# 32u4_with_A9G_GPRS_GSM_GPS_v1_0.net
KiCad netlist of a schematic drawn in EAGLE
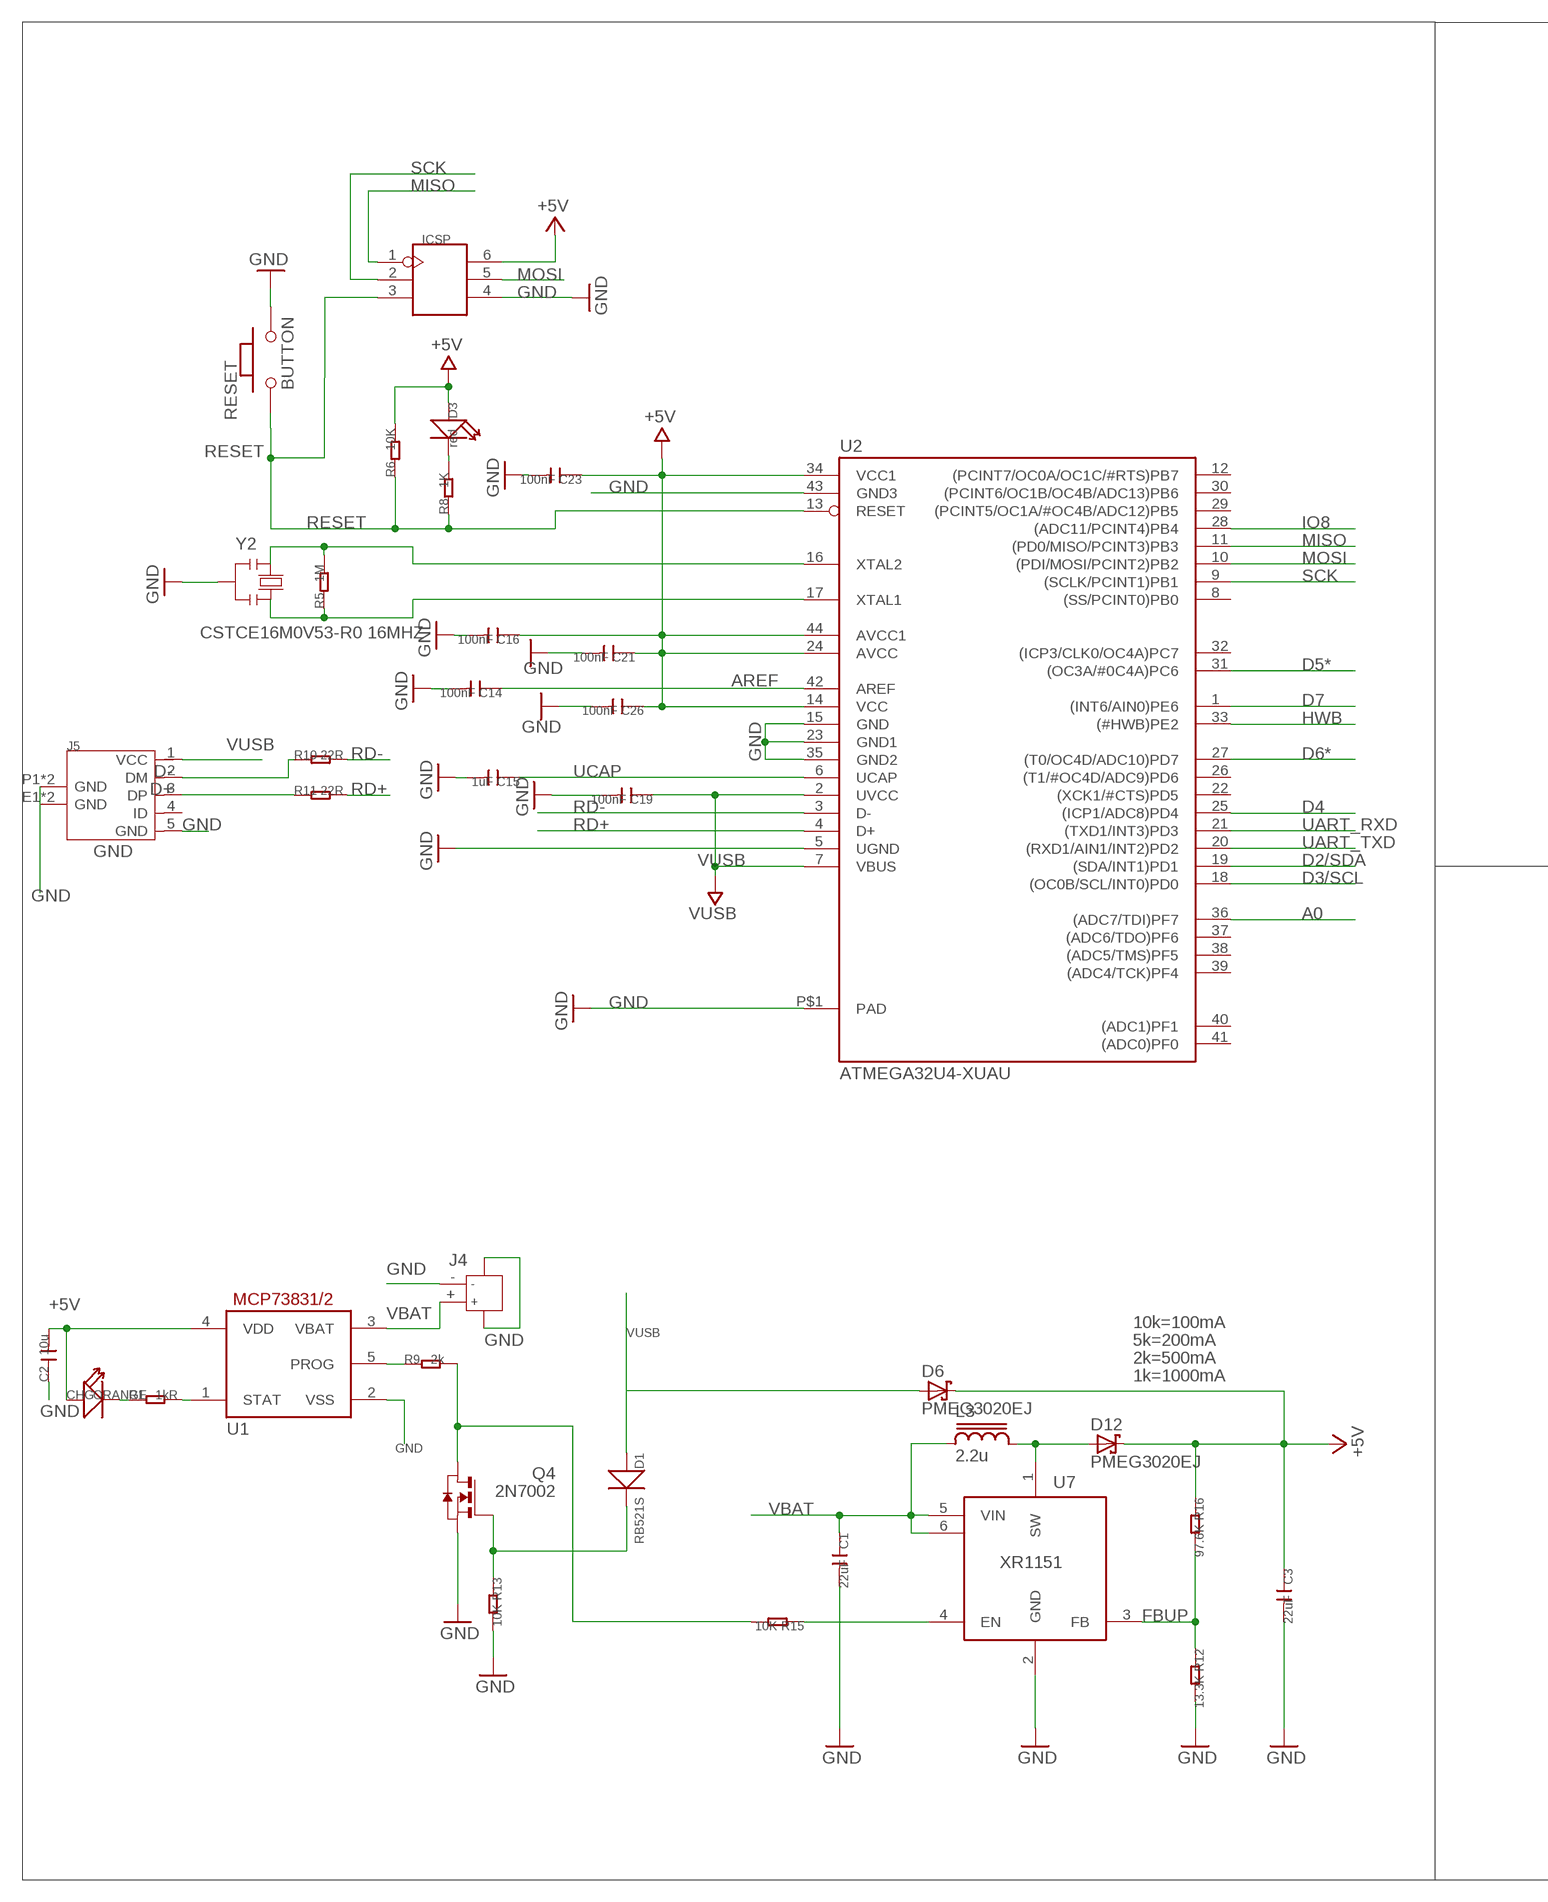
[diagram p0: schematic, sheet 1, part 1 of 2]
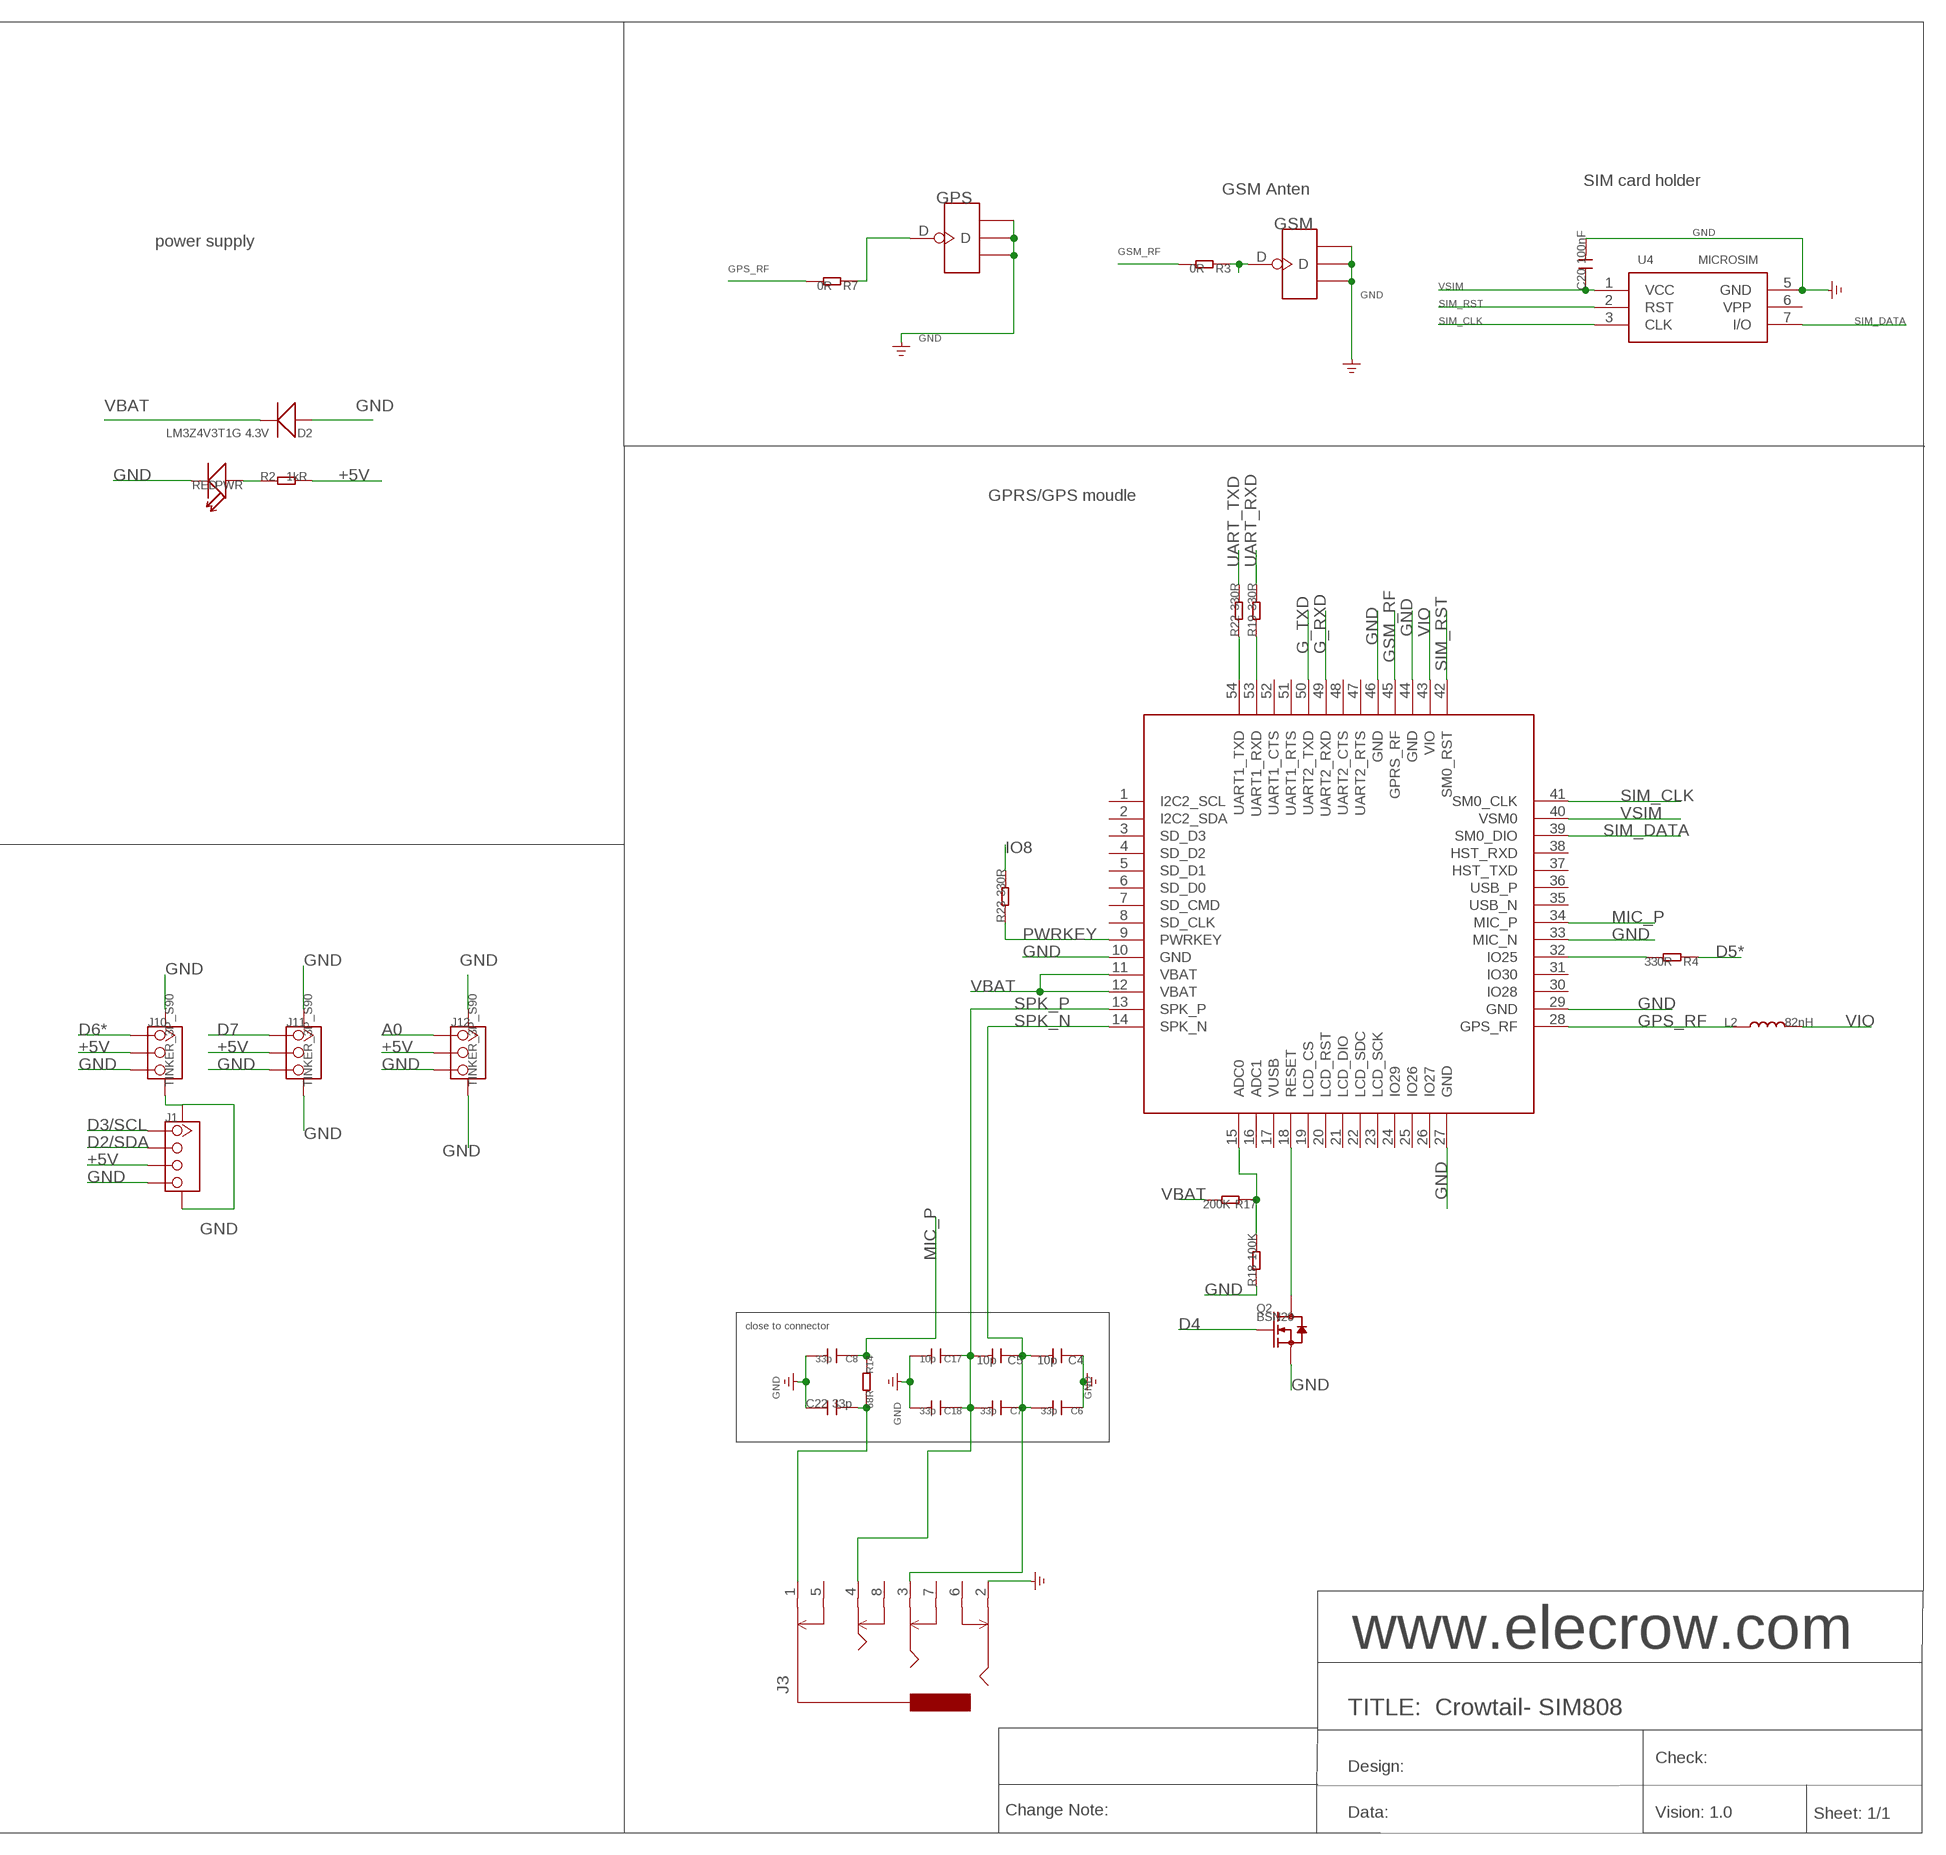
[diagram p1: schematic, sheet 1, part 2 of 2]

(export (version "E")
  (design (tool "Eeschema 10.0.6"))
  (components
    (comp (ref "C1")
      (value "22uF")
      (footprint "eagle-import:C0603")
      (libsource (lib "eagle-import") (part "C-0603"))
    )
    (comp (ref "C2")
      (value "10u")
      (footprint "eagle-import:C0603")
      (libsource (lib "eagle-import") (part "C-0603"))
    )
    (comp (ref "C3")
      (value "22uF")
      (footprint "eagle-import:C0603")
      (libsource (lib "eagle-import") (part "C-0603"))
    )
    (comp (ref "C4")
      (value "10p")
      (footprint "eagle-import:C0402")
      (libsource (lib "eagle-import") (part "C-0402"))
    )
    (comp (ref "C5")
      (value "10p")
      (footprint "eagle-import:C0402")
      (libsource (lib "eagle-import") (part "C-0402"))
    )
    (comp (ref "C6")
      (value "33p")
      (footprint "eagle-import:C0402")
      (libsource (lib "eagle-import") (part "C-0402"))
    )
    (comp (ref "C7")
      (value "33p")
      (footprint "eagle-import:C0402")
      (libsource (lib "eagle-import") (part "C-0402"))
    )
    (comp (ref "C8")
      (value "33p")
      (footprint "eagle-import:C0603")
      (libsource (lib "eagle-import") (part "C-0603"))
    )
    (comp (ref "C14")
      (value "100nF")
      (footprint "eagle-import:C0603")
      (libsource (lib "eagle-import") (part "C-0603"))
    )
    (comp (ref "C15")
      (value "1uF")
      (footprint "eagle-import:C0603")
      (libsource (lib "eagle-import") (part "C-0603"))
    )
    (comp (ref "C16")
      (value "100nF")
      (footprint "eagle-import:C0603")
      (libsource (lib "eagle-import") (part "C-0603"))
    )
    (comp (ref "C17")
      (value "10p")
      (footprint "eagle-import:C0402")
      (libsource (lib "eagle-import") (part "C-0402"))
    )
    (comp (ref "C18")
      (value "33p")
      (footprint "eagle-import:C0402")
      (libsource (lib "eagle-import") (part "C-0402"))
    )
    (comp (ref "C19")
      (value "100nF")
      (footprint "eagle-import:C0603")
      (libsource (lib "eagle-import") (part "C-0603"))
    )
    (comp (ref "C20")
      (value "100nF")
      (footprint "eagle-import:C0603")
      (libsource (lib "eagle-import") (part "C-0603"))
    )
    (comp (ref "C21")
      (value "100nF")
      (footprint "eagle-import:C0603")
      (libsource (lib "eagle-import") (part "C-0603"))
    )
    (comp (ref "C22")
      (value "33p")
      (footprint "eagle-import:C0603")
      (libsource (lib "eagle-import") (part "C-0603"))
    )
    (comp (ref "C23")
      (value "100nF")
      (footprint "eagle-import:C0603")
      (libsource (lib "eagle-import") (part "C-0603"))
    )
    (comp (ref "C26")
      (value "100nF")
      (footprint "eagle-import:C0603")
      (libsource (lib "eagle-import") (part "C-0603"))
    )
    (comp (ref "CHG")
      (value "ORANGE")
      (footprint "eagle-import:D0603")
      (libsource (lib "eagle-import") (part "007-LED0603"))
    )
    (comp (ref "D1")
      (value "RB521S")
      (footprint "eagle-import:SOD523")
      (libsource (lib "eagle-import") (part "D'0603'"))
    )
    (comp (ref "D2")
      (value "LM3Z4V3T1G 4.3V")
      (footprint "eagle-import:SOD323")
      (libsource (lib "eagle-import") (part "D'0805'"))
    )
    (comp (ref "D3")
      (value "red")
      (footprint "eagle-import:LED-0603")
      (libsource (lib "eagle-import") (part "LED'0603'"))
    )
    (comp (ref "D6")
      (value "PMEG3020EJ")
      (footprint "eagle-import:SOD-323")
      (libsource (lib "eagle-import") (part "PMEG3020EJ"))
    )
    (comp (ref "D12")
      (value "PMEG3020EJ")
      (footprint "eagle-import:SOD-323")
      (libsource (lib "eagle-import") (part "PMEG3020EJ"))
    )
    (comp (ref "GPS")
      (value "ANTENNA-U-FL")
      (footprint "eagle-import:4P-U-FL")
      (libsource (lib "eagle-import") (part "ANTENNA-U-FL"))
    )
    (comp (ref "GSM")
      (value "ANTENNA-U-FL")
      (footprint "eagle-import:4P-U-FL")
      (libsource (lib "eagle-import") (part "ANTENNA-U-FL"))
    )
    (comp (ref "ICSP")
      (value "HEADER-2X3P-2.0")
      (footprint "eagle-import:2X3P-2.0")
      (libsource (lib "eagle-import") (part "HEADER-2X3P-2.0"))
    )
    (comp (ref "J1")
      (value "TWIG-4P-2.0-SMD-FEMALE-REINFORCE'90D'")
      (footprint "eagle-import:4P-SMD-2.0-90D")
      (libsource (lib "eagle-import") (part "TWIG-4P-2.0-SMD-FEMALE-REINFORCE'90D'"))
    )
    (comp (ref "J3")
      (value "AUDIO-8P'PJ-3536-L6S'")
      (footprint "eagle-import:8P-3.5-SMD")
      (libsource (lib "eagle-import") (part "AUDIO-8P'PJ-3536-L6S'"))
    )
    (comp (ref "J4")
      (value "JACK-JST-2P-SMD-PW'2.0'")
      (footprint "eagle-import:JST-SMD-2.0-90D")
      (libsource (lib "eagle-import") (part "JACK-JST-2P-SMD-PW'2.0'"))
    )
    (comp (ref "J5")
      (value "MICRO-USB-5P-340015001")
      (footprint "eagle-import:B-SMD-5P")
      (libsource (lib "eagle-import") (part "MICRO-USB-5P-340015001"))
    )
    (comp (ref "J10")
      (value "TINKER_3P_S90")
      (footprint "eagle-import:TINKER_3P_S90")
      (libsource (lib "eagle-import") (part "TINKER_3P_S90"))
    )
    (comp (ref "J11")
      (value "TINKER_3P_S90")
      (footprint "eagle-import:TINKER_3P_S90")
      (libsource (lib "eagle-import") (part "TINKER_3P_S90"))
    )
    (comp (ref "J12")
      (value "TINKER_3P_S90")
      (footprint "eagle-import:TINKER_3P_S90")
      (libsource (lib "eagle-import") (part "TINKER_3P_S90"))
    )
    (comp (ref "L2")
      (value "82nH")
      (footprint "eagle-import:L0603")
      (libsource (lib "eagle-import") (part "L'0603'"))
    )
    (comp (ref "L3")
      (value "2.2u")
      (footprint "eagle-import:CD32")
      (libsource (lib "eagle-import") (part "LCD32"))
    )
    (comp (ref "PWR")
      (value "RED")
      (footprint "eagle-import:D0603")
      (libsource (lib "eagle-import") (part "007-LED0603"))
    )
    (comp (ref "Q2")
      (value "BSN20")
      (footprint "eagle-import:SOT23@1")
      (libsource (lib "eagle-import") (part "MOSFET-N'SOT23'"))
    )
    (comp (ref "Q4")
      (value "2N7002")
      (footprint "eagle-import:SOT23")
      (libsource (lib "eagle-import") (part "2N7002"))
    )
    (comp (ref "R1")
      (value "1kR")
      (footprint "eagle-import:R0603")
      (libsource (lib "eagle-import") (part "R-0603"))
    )
    (comp (ref "R2")
      (value "1kR")
      (footprint "eagle-import:R0603")
      (libsource (lib "eagle-import") (part "R-0603"))
    )
    (comp (ref "R3")
      (value "0R")
      (footprint "eagle-import:R0603")
      (libsource (lib "eagle-import") (part "R-0603"))
    )
    (comp (ref "R4")
      (value "330R")
      (footprint "eagle-import:R0603")
      (libsource (lib "eagle-import") (part "R-0603"))
    )
    (comp (ref "R5")
      (value "1M")
      (footprint "eagle-import:R0603")
      (libsource (lib "eagle-import") (part "R-0603"))
    )
    (comp (ref "R6")
      (value "10K")
      (footprint "eagle-import:R0603")
      (libsource (lib "eagle-import") (part "R-0603"))
    )
    (comp (ref "R7")
      (value "0R")
      (footprint "eagle-import:R0603")
      (libsource (lib "eagle-import") (part "R-0603"))
    )
    (comp (ref "R8")
      (value "1K")
      (footprint "eagle-import:R0603")
      (libsource (lib "eagle-import") (part "R-0603"))
    )
    (comp (ref "R9")
      (value "2k")
      (footprint "eagle-import:R0603")
      (libsource (lib "eagle-import") (part "R-0603"))
    )
    (comp (ref "R10")
      (value "22R")
      (footprint "eagle-import:R0603")
      (libsource (lib "eagle-import") (part "R-0603"))
    )
    (comp (ref "R11")
      (value "22R")
      (footprint "eagle-import:R0603")
      (libsource (lib "eagle-import") (part "R-0603"))
    )
    (comp (ref "R12")
      (value "13.3K")
      (footprint "eagle-import:R0603")
      (libsource (lib "eagle-import") (part "R-0603"))
    )
    (comp (ref "R13")
      (value "10K")
      (footprint "eagle-import:R0603")
      (libsource (lib "eagle-import") (part "R-0603"))
    )
    (comp (ref "R14")
      (value "68R")
      (footprint "eagle-import:R0603")
      (libsource (lib "eagle-import") (part "R-0603"))
    )
    (comp (ref "R15")
      (value "10K")
      (footprint "eagle-import:R0603")
      (libsource (lib "eagle-import") (part "R-0603"))
    )
    (comp (ref "R16")
      (value "97.6K")
      (footprint "eagle-import:R0603")
      (libsource (lib "eagle-import") (part "R-0603"))
    )
    (comp (ref "R17")
      (value "200K")
      (footprint "eagle-import:R0603")
      (libsource (lib "eagle-import") (part "R-0603"))
    )
    (comp (ref "R18")
      (value "100K")
      (footprint "eagle-import:R0603")
      (libsource (lib "eagle-import") (part "R-0603"))
    )
    (comp (ref "R19")
      (value "330R")
      (footprint "eagle-import:R0603")
      (libsource (lib "eagle-import") (part "R-0603"))
    )
    (comp (ref "R22")
      (value "330R")
      (footprint "eagle-import:R0603")
      (libsource (lib "eagle-import") (part "R-0603"))
    )
    (comp (ref "R23")
      (value "330R")
      (footprint "eagle-import:R0603")
      (libsource (lib "eagle-import") (part "R-0603"))
    )
    (comp (ref "RESET")
      (value "BUTTON")
      (footprint "eagle-import:157SW")
      (libsource (lib "eagle-import") (part "PB157"))
    )
    (comp (ref "U1")
      (value "MCP73831/OT")
      (footprint "eagle-import:SOT23-5L")
      (libsource (lib "eagle-import") (part "MCP73831/OT"))
    )
    (comp (ref "U2")
      (value "ATMEGA32U4-XUAU")
      (footprint "eagle-import:TQFP44-PAD")
      (libsource (lib "eagle-import") (part "ATMEGA32U4-XUAU"))
    )
    (comp (ref "U4")
      (value "MICROSIM")
      (footprint "eagle-import:MICROSIM")
      (libsource (lib "eagle-import") (part "MICROSIM"))
    )
    (comp (ref "U5")
      (value "A9G")
      (footprint "eagle-import:A9G")
      (libsource (lib "eagle-import") (part "A9G"))
    )
    (comp (ref "U7")
      (value "XR1151")
      (footprint "eagle-import:SOT23-6L")
      (libsource (lib "eagle-import") (part "XR1151"))
    )
    (comp (ref "Y2")
      (value "CSTCE16M0V53-R0 16MHZ")
      (footprint "eagle-import:RESONATOR")
      (libsource (lib "eagle-import") (part "RESONATORMU"))
    )
  )
  (nets
    (net (code "1") (name "+5V") (class "Default")
      (node (ref "C16") (pin "1") (pinfunction "1_1") (pintype "passive"))
      (node (ref "C2") (pin "2") (pinfunction "2_2") (pintype "passive"))
      (node (ref "C21") (pin "1") (pinfunction "1_1") (pintype "passive"))
      (node (ref "C23") (pin "1") (pinfunction "1_1") (pintype "passive"))
      (node (ref "C26") (pin "1") (pinfunction "1_1") (pintype "passive"))
      (node (ref "C3") (pin "1") (pinfunction "1_1") (pintype "passive"))
      (node (ref "CHG") (pin "+") (pinfunction "+_+") (pintype "passive"))
      (node (ref "D12") (pin "C") (pinfunction "C_C") (pintype "passive"))
      (node (ref "D3") (pin "+") (pinfunction "+_+") (pintype "passive"))
      (node (ref "D6") (pin "C") (pinfunction "C_C") (pintype "passive"))
      (node (ref "ICSP") (pin "6") (pinfunction "6_6") (pintype "bidirectional"))
      (node (ref "J1") (pin "3") (pinfunction "3_3") (pintype "bidirectional"))
      (node (ref "J10") (pin "2") (pinfunction "2_2") (pintype "bidirectional"))
      (node (ref "J11") (pin "2") (pinfunction "2_2") (pintype "bidirectional"))
      (node (ref "J12") (pin "2") (pinfunction "2_2") (pintype "bidirectional"))
      (node (ref "R16") (pin "1") (pinfunction "1_1") (pintype "passive"))
      (node (ref "R2") (pin "2") (pinfunction "2_2") (pintype "passive"))
      (node (ref "R6") (pin "2") (pinfunction "2_2") (pintype "passive"))
      (node (ref "U1") (pin "4") (pinfunction "VDD_4") (pintype "power_in"))
      (node (ref "U2") (pin "14") (pinfunction "VCC_14") (pintype "power_in"))
      (node (ref "U2") (pin "24") (pinfunction "AVCC_24") (pintype "power_in"))
      (node (ref "U2") (pin "34") (pinfunction "VCC1_34") (pintype "power_in"))
      (node (ref "U2") (pin "44") (pinfunction "AVCC1_44") (pintype "power_in"))
    )
    (net (code "2") (name "/A0") (class "Default")
      (node (ref "J12") (pin "1") (pinfunction "1_1") (pintype "bidirectional"))
      (node (ref "U2") (pin "36") (pinfunction "(ADC7/TDI)PF7_36") (pintype "bidirectional"))
    )
    (net (code "3") (name "/AREF") (class "Default")
      (node (ref "C14") (pin "1") (pinfunction "1_1") (pintype "passive"))
      (node (ref "U2") (pin "42") (pinfunction "AREF_42") (pintype "power_in"))
    )
    (net (code "4") (name "/D+") (class "Default")
      (node (ref "J5") (pin "3") (pinfunction "DP_3") (pintype "bidirectional"))
      (node (ref "R11") (pin "1") (pinfunction "1_1") (pintype "passive"))
    )
    (net (code "5") (name "/D-") (class "Default")
      (node (ref "J5") (pin "2") (pinfunction "DM_2") (pintype "bidirectional"))
      (node (ref "R10") (pin "1") (pinfunction "1_1") (pintype "passive"))
    )
    (net (code "6") (name "/D2{slash}SDA") (class "Default")
      (node (ref "J1") (pin "2") (pinfunction "2_2") (pintype "bidirectional"))
      (node (ref "U2") (pin "19") (pinfunction "(SDA/INT1)PD1_19") (pintype "bidirectional"))
    )
    (net (code "7") (name "/D3{slash}SCL") (class "Default")
      (node (ref "J1") (pin "1") (pinfunction "1_1") (pintype "bidirectional"))
      (node (ref "U2") (pin "18") (pinfunction "(OC0B/SCL/INT0)PD0_18") (pintype "bidirectional"))
    )
    (net (code "8") (name "/D4") (class "Default")
      (node (ref "Q2") (pin "1") (pinfunction "G_1") (pintype "passive"))
      (node (ref "U2") (pin "25") (pinfunction "(ICP1/ADC8)PD4_25") (pintype "bidirectional"))
    )
    (net (code "9") (name "/D5*") (class "Default")
      (node (ref "R4") (pin "1") (pinfunction "1_1") (pintype "passive"))
      (node (ref "U2") (pin "31") (pinfunction "(OC3A/#0C4A)PC6_31") (pintype "bidirectional"))
    )
    (net (code "10") (name "/D6*") (class "Default")
      (node (ref "J10") (pin "1") (pinfunction "1_1") (pintype "bidirectional"))
      (node (ref "U2") (pin "27") (pinfunction "(T0/OC4D/ADC10)PD7_27") (pintype "bidirectional"))
    )
    (net (code "11") (name "/D7") (class "Default")
      (node (ref "J11") (pin "1") (pinfunction "1_1") (pintype "bidirectional"))
      (node (ref "U2") (pin "1") (pinfunction "(INT6/AIN0)PE6_1") (pintype "bidirectional"))
    )
    (net (code "12") (name "/FBUP") (class "Default")
      (node (ref "R12") (pin "1") (pinfunction "1_1") (pintype "passive"))
      (node (ref "R16") (pin "2") (pinfunction "2_2") (pintype "passive"))
      (node (ref "U7") (pin "3") (pinfunction "FB_3") (pintype "input"))
    )
    (net (code "13") (name "/GPS_RF") (class "Default")
      (node (ref "L2") (pin "1") (pinfunction "1_1") (pintype "passive"))
      (node (ref "R7") (pin "2") (pinfunction "2_2") (pintype "passive"))
      (node (ref "U5") (pin "28") (pinfunction "GPS_RF_28") (pintype "bidirectional"))
    )
    (net (code "14") (name "/GSM_RF") (class "Default")
      (node (ref "R3") (pin "2") (pinfunction "2_2") (pintype "passive"))
      (node (ref "U5") (pin "45") (pinfunction "GPRS_RF_45") (pintype "bidirectional"))
    )
    (net (code "15") (name "/G_RXD") (class "Default")
      (node (ref "U5") (pin "49") (pinfunction "UART2_RXD_49") (pintype "bidirectional"))
    )
    (net (code "16") (name "/G_TXD") (class "Default")
      (node (ref "U5") (pin "50") (pinfunction "UART2_TXD_50") (pintype "bidirectional"))
    )
    (net (code "17") (name "/HWB") (class "Default")
      (node (ref "U2") (pin "33") (pinfunction "(#HWB)PE2_33") (pintype "bidirectional"))
    )
    (net (code "18") (name "/IO8") (class "Default")
      (node (ref "R23") (pin "2") (pinfunction "2_2") (pintype "passive"))
      (node (ref "U2") (pin "28") (pinfunction "(ADC11/PCINT4)PB4_28") (pintype "bidirectional"))
    )
    (net (code "19") (name "/MIC_P") (class "Default")
      (node (ref "C8") (pin "1") (pinfunction "1_1") (pintype "passive"))
      (node (ref "R14") (pin "1") (pinfunction "1_1") (pintype "passive"))
      (node (ref "U5") (pin "34") (pinfunction "MIC_P_34") (pintype "bidirectional"))
    )
    (net (code "20") (name "/MISO") (class "Default")
      (node (ref "ICSP") (pin "1") (pinfunction "1_1") (pintype "bidirectional"))
      (node (ref "U2") (pin "11") (pinfunction "(PD0/MISO/PCINT3)PB3_11") (pintype "bidirectional"))
    )
    (net (code "21") (name "/MOSI") (class "Default")
      (node (ref "ICSP") (pin "5") (pinfunction "5_5") (pintype "bidirectional"))
      (node (ref "U2") (pin "10") (pinfunction "(PDI/MOSI/PCINT2)PB2_10") (pintype "bidirectional"))
    )
    (net (code "22") (name "/PWRKEY") (class "Default")
      (node (ref "R23") (pin "1") (pinfunction "1_1") (pintype "passive"))
      (node (ref "U5") (pin "9") (pinfunction "PWRKEY_9") (pintype "bidirectional"))
    )
    (net (code "23") (name "/RD+") (class "Default")
      (node (ref "R11") (pin "2") (pinfunction "2_2") (pintype "passive"))
      (node (ref "U2") (pin "4") (pinfunction "D+_4") (pintype "bidirectional"))
    )
    (net (code "24") (name "/RD-") (class "Default")
      (node (ref "R10") (pin "2") (pinfunction "2_2") (pintype "passive"))
      (node (ref "U2") (pin "3") (pinfunction "D-_3") (pintype "bidirectional"))
    )
    (net (code "25") (name "/RESET") (class "Default")
      (node (ref "ICSP") (pin "3") (pinfunction "3_3") (pintype "bidirectional"))
      (node (ref "R6") (pin "1") (pinfunction "1_1") (pintype "passive"))
      (node (ref "R8") (pin "1") (pinfunction "1_1") (pintype "passive"))
      (node (ref "RESET") (pin "1") (pinfunction "1_1") (pintype "passive"))
      (node (ref "U2") (pin "13") (pinfunction "RESET_13") (pintype "input"))
    )
    (net (code "26") (name "/SCK") (class "Default")
      (node (ref "ICSP") (pin "2") (pinfunction "2_2") (pintype "bidirectional"))
      (node (ref "U2") (pin "9") (pinfunction "(SCLK/PCINT1)PB1_9") (pintype "bidirectional"))
    )
    (net (code "27") (name "/SIM_CLK") (class "Default")
      (node (ref "U4") (pin "3") (pinfunction "CLK_3") (pintype "bidirectional"))
      (node (ref "U5") (pin "41") (pinfunction "SM0_CLK_41") (pintype "bidirectional"))
    )
    (net (code "28") (name "/SIM_DATA") (class "Default")
      (node (ref "U4") (pin "7") (pinfunction "I/O_7") (pintype "bidirectional"))
      (node (ref "U5") (pin "39") (pinfunction "SM0_DIO_39") (pintype "bidirectional"))
    )
    (net (code "29") (name "/SIM_RST") (class "Default")
      (node (ref "U4") (pin "2") (pinfunction "RST_2") (pintype "bidirectional"))
      (node (ref "U5") (pin "42") (pinfunction "SM0_RST_42") (pintype "bidirectional"))
    )
    (net (code "30") (name "/SPK_N") (class "Default")
      (node (ref "C4") (pin "2") (pinfunction "2_2") (pintype "passive"))
      (node (ref "C5") (pin "1") (pinfunction "1_1") (pintype "passive"))
      (node (ref "C6") (pin "2") (pinfunction "2_2") (pintype "passive"))
      (node (ref "C7") (pin "1") (pinfunction "1_1") (pintype "passive"))
      (node (ref "J3") (pin "3") (pinfunction "3_3") (pintype "bidirectional"))
      (node (ref "U5") (pin "14") (pinfunction "SPK_N_14") (pintype "bidirectional"))
    )
    (net (code "31") (name "/SPK_P") (class "Default")
      (node (ref "C17") (pin "1") (pinfunction "1_1") (pintype "passive"))
      (node (ref "C18") (pin "1") (pinfunction "1_1") (pintype "passive"))
      (node (ref "C5") (pin "2") (pinfunction "2_2") (pintype "passive"))
      (node (ref "C7") (pin "2") (pinfunction "2_2") (pintype "passive"))
      (node (ref "J3") (pin "4") (pinfunction "4_4") (pintype "bidirectional"))
      (node (ref "U5") (pin "13") (pinfunction "SPK_P_13") (pintype "bidirectional"))
    )
    (net (code "32") (name "/UART_RXD") (class "Default")
      (node (ref "R19") (pin "2") (pinfunction "2_2") (pintype "passive"))
      (node (ref "U2") (pin "21") (pinfunction "(TXD1/INT3)PD3_21") (pintype "bidirectional"))
    )
    (net (code "33") (name "/UART_TXD") (class "Default")
      (node (ref "R22") (pin "2") (pinfunction "2_2") (pintype "passive"))
      (node (ref "U2") (pin "20") (pinfunction "(RXD1/AIN1/INT2)PD2_20") (pintype "bidirectional"))
    )
    (net (code "34") (name "/UCAP") (class "Default")
      (node (ref "C15") (pin "1") (pinfunction "1_1") (pintype "passive"))
      (node (ref "U2") (pin "6") (pinfunction "UCAP_6") (pintype "passive"))
    )
    (net (code "35") (name "/VBAT") (class "Default")
      (node (ref "C1") (pin "1") (pinfunction "1_1") (pintype "passive"))
      (node (ref "D2") (pin "-") (pinfunction "-_-") (pintype "passive"))
      (node (ref "J4") (pin "+") (pinfunction "1_+") (pintype "bidirectional"))
      (node (ref "L3") (pin "1") (pinfunction "1_1") (pintype "passive"))
      (node (ref "R17") (pin "2") (pinfunction "2_2") (pintype "passive"))
      (node (ref "U1") (pin "3") (pinfunction "VBAT_3") (pintype "bidirectional"))
      (node (ref "U5") (pin "11") (pinfunction "VBAT_11") (pintype "bidirectional"))
      (node (ref "U5") (pin "12") (pinfunction "VBAT_12") (pintype "bidirectional"))
      (node (ref "U7") (pin "5") (pinfunction "VIN_5") (pintype "power_in"))
      (node (ref "U7") (pin "6") (pinfunction "VIN1_6") (pintype "power_in"))
    )
    (net (code "36") (name "/VIO") (class "Default")
      (node (ref "L2") (pin "2") (pinfunction "2_2") (pintype "passive"))
      (node (ref "U5") (pin "43") (pinfunction "VIO_43") (pintype "bidirectional"))
    )
    (net (code "37") (name "/VSIM") (class "Default")
      (node (ref "C20") (pin "1") (pinfunction "1_1") (pintype "passive"))
      (node (ref "U4") (pin "1") (pinfunction "VCC_1") (pintype "bidirectional"))
      (node (ref "U5") (pin "40") (pinfunction "VSM0_40") (pintype "bidirectional"))
    )
    (net (code "38") (name "GND") (class "Default")
      (node (ref "C1") (pin "2") (pinfunction "2_2") (pintype "passive"))
      (node (ref "C14") (pin "2") (pinfunction "2_2") (pintype "passive"))
      (node (ref "C15") (pin "2") (pinfunction "2_2") (pintype "passive"))
      (node (ref "C16") (pin "2") (pinfunction "2_2") (pintype "passive"))
      (node (ref "C17") (pin "2") (pinfunction "2_2") (pintype "passive"))
      (node (ref "C18") (pin "2") (pinfunction "2_2") (pintype "passive"))
      (node (ref "C19") (pin "2") (pinfunction "2_2") (pintype "passive"))
      (node (ref "C2") (pin "1") (pinfunction "1_1") (pintype "passive"))
      (node (ref "C20") (pin "2") (pinfunction "2_2") (pintype "passive"))
      (node (ref "C21") (pin "2") (pinfunction "2_2") (pintype "passive"))
      (node (ref "C22") (pin "1") (pinfunction "1_1") (pintype "passive"))
      (node (ref "C23") (pin "2") (pinfunction "2_2") (pintype "passive"))
      (node (ref "C26") (pin "2") (pinfunction "2_2") (pintype "passive"))
      (node (ref "C3") (pin "2") (pinfunction "2_2") (pintype "passive"))
      (node (ref "C4") (pin "1") (pinfunction "1_1") (pintype "passive"))
      (node (ref "C6") (pin "1") (pinfunction "1_1") (pintype "passive"))
      (node (ref "C8") (pin "2") (pinfunction "2_2") (pintype "passive"))
      (node (ref "D2") (pin "+") (pinfunction "+_+") (pintype "passive"))
      (node (ref "GPS") (pin "GND1") (pinfunction "GND1_GND1") (pintype "bidirectional"))
      (node (ref "GPS") (pin "GND2") (pinfunction "GND2_GND2") (pintype "bidirectional"))
      (node (ref "GPS") (pin "GND3") (pinfunction "GND3_GND3") (pintype "bidirectional"))
      (node (ref "GSM") (pin "GND1") (pinfunction "GND1_GND1") (pintype "bidirectional"))
      (node (ref "GSM") (pin "GND2") (pinfunction "GND2_GND2") (pintype "bidirectional"))
      (node (ref "GSM") (pin "GND3") (pinfunction "GND3_GND3") (pintype "bidirectional"))
      (node (ref "ICSP") (pin "4") (pinfunction "4_4") (pintype "bidirectional"))
      (node (ref "J1") (pin "4") (pinfunction "4_4") (pintype "bidirectional"))
      (node (ref "J1") (pin "SS1") (pinfunction "SS1_SS1") (pintype "bidirectional"))
      (node (ref "J1") (pin "SS2") (pinfunction "SS2_SS2") (pintype "bidirectional"))
      (node (ref "J10") (pin "3") (pinfunction "3_3") (pintype "bidirectional"))
      (node (ref "J10") (pin "SS1") (pinfunction "SS1_SS1") (pintype "bidirectional"))
      (node (ref "J10") (pin "SS2") (pinfunction "SS2_SS2") (pintype "bidirectional"))
      (node (ref "J11") (pin "3") (pinfunction "3_3") (pintype "bidirectional"))
      (node (ref "J11") (pin "SS1") (pinfunction "SS1_SS1") (pintype "bidirectional"))
      (node (ref "J11") (pin "SS2") (pinfunction "SS2_SS2") (pintype "bidirectional"))
      (node (ref "J12") (pin "3") (pinfunction "3_3") (pintype "bidirectional"))
      (node (ref "J12") (pin "SS1") (pinfunction "SS1_SS1") (pintype "bidirectional"))
      (node (ref "J12") (pin "SS2") (pinfunction "SS2_SS2") (pintype "bidirectional"))
      (node (ref "J3") (pin "2") (pinfunction "2_2") (pintype "bidirectional"))
      (node (ref "J4") (pin "-") (pinfunction "2_-") (pintype "bidirectional"))
      (node (ref "J4") (pin "3") (pinfunction "3_3") (pintype "bidirectional"))
      (node (ref "J4") (pin "4") (pinfunction "4_4") (pintype "bidirectional"))
      (node (ref "J5") (pin "5") (pinfunction "GND_5") (pintype "bidirectional"))
      (node (ref "J5") (pin "E1") (pinfunction "GND_E1") (pintype "bidirectional"))
      (node (ref "J5") (pin "E2") (pinfunction "GND_E2") (pintype "bidirectional"))
      (node (ref "J5") (pin "P1") (pinfunction "GND_P1") (pintype "bidirectional"))
      (node (ref "J5") (pin "P2") (pinfunction "GND_P2") (pintype "bidirectional"))
      (node (ref "PWR") (pin "-") (pinfunction "-_-") (pintype "passive"))
      (node (ref "Q2") (pin "2") (pinfunction "S_2") (pintype "passive"))
      (node (ref "Q4") (pin "2") (pinfunction "S_2") (pintype "passive"))
      (node (ref "R12") (pin "2") (pinfunction "2_2") (pintype "passive"))
      (node (ref "R13") (pin "2") (pinfunction "2_2") (pintype "passive"))
      (node (ref "R18") (pin "1") (pinfunction "1_1") (pintype "passive"))
      (node (ref "RESET") (pin "2") (pinfunction "2_2") (pintype "passive"))
      (node (ref "U1") (pin "2") (pinfunction "VSS_2") (pintype "power_in"))
      (node (ref "U2") (pin "15") (pinfunction "GND_15") (pintype "power_in"))
      (node (ref "U2") (pin "23") (pinfunction "GND1_23") (pintype "power_in"))
      (node (ref "U2") (pin "35") (pinfunction "GND2_35") (pintype "power_in"))
      (node (ref "U2") (pin "43") (pinfunction "GND3_43") (pintype "power_in"))
      (node (ref "U2") (pin "5") (pinfunction "UGND_5") (pintype "power_in"))
      (node (ref "U2") (pin "P$1") (pinfunction "PAD_P$1") (pintype "power_in"))
      (node (ref "U4") (pin "5") (pinfunction "GND_5") (pintype "bidirectional"))
      (node (ref "U5") (pin "10") (pinfunction "GND_10") (pintype "bidirectional"))
      (node (ref "U5") (pin "27") (pinfunction "GND_27") (pintype "bidirectional"))
      (node (ref "U5") (pin "29") (pinfunction "GND_29") (pintype "bidirectional"))
      (node (ref "U5") (pin "33") (pinfunction "MIC_N_33") (pintype "bidirectional"))
      (node (ref "U5") (pin "44") (pinfunction "GND_44") (pintype "bidirectional"))
      (node (ref "U5") (pin "46") (pinfunction "GND_46") (pintype "bidirectional"))
      (node (ref "U7") (pin "2") (pinfunction "GND_2") (pintype "power_in"))
      (node (ref "Y2") (pin "2") (pinfunction "2_2") (pintype "passive"))
    )
    (net (code "39") (name "Net-(C22-Pad2)") (class "Default")
      (node (ref "C22") (pin "2") (pinfunction "2_2") (pintype "passive"))
      (node (ref "J3") (pin "1") (pinfunction "1_1") (pintype "bidirectional"))
      (node (ref "R14") (pin "2") (pinfunction "2_2") (pintype "passive"))
    )
    (net (code "40") (name "Net-(CHG-Pad-)") (class "Default")
      (node (ref "CHG") (pin "-") (pinfunction "-_-") (pintype "passive"))
      (node (ref "R1") (pin "1") (pinfunction "1_1") (pintype "passive"))
    )
    (net (code "41") (name "Net-(D3-Pad-)") (class "Default")
      (node (ref "D3") (pin "-") (pinfunction "-_-") (pintype "passive"))
      (node (ref "R8") (pin "2") (pinfunction "2_2") (pintype "passive"))
    )
    (net (code "42") (name "Net-(GPS-PadD)") (class "Default")
      (node (ref "GPS") (pin "D") (pinfunction "D_D") (pintype "bidirectional"))
      (node (ref "R7") (pin "1") (pinfunction "1_1") (pintype "passive"))
    )
    (net (code "43") (name "Net-(GSM-PadD)") (class "Default")
      (node (ref "GSM") (pin "D") (pinfunction "D_D") (pintype "bidirectional"))
      (node (ref "R3") (pin "1") (pinfunction "1_1") (pintype "passive"))
    )
    (net (code "44") (name "Net-(PWR-Pad+)") (class "Default")
      (node (ref "PWR") (pin "+") (pinfunction "+_+") (pintype "passive"))
      (node (ref "R2") (pin "1") (pinfunction "1_1") (pintype "passive"))
    )
    (net (code "45") (name "Net-(Q2-D)") (class "Default")
      (node (ref "Q2") (pin "3") (pinfunction "D_3") (pintype "passive"))
      (node (ref "U5") (pin "18") (pinfunction "RESET_18") (pintype "bidirectional"))
    )
    (net (code "46") (name "Net-(Q4-D)") (class "Default")
      (node (ref "Q4") (pin "3") (pinfunction "D_3") (pintype "passive"))
      (node (ref "R15") (pin "2") (pinfunction "2_2") (pintype "passive"))
      (node (ref "R9") (pin "2") (pinfunction "2_2") (pintype "passive"))
    )
    (net (code "47") (name "Net-(Q4-G)") (class "Default")
      (node (ref "D1") (pin "-") (pinfunction "-_-") (pintype "passive"))
      (node (ref "Q4") (pin "1") (pinfunction "G_1") (pintype "passive"))
      (node (ref "R13") (pin "1") (pinfunction "1_1") (pintype "passive"))
    )
    (net (code "48") (name "Net-(U1-PROG)") (class "Default")
      (node (ref "R9") (pin "1") (pinfunction "1_1") (pintype "passive"))
      (node (ref "U1") (pin "5") (pinfunction "PROG_5") (pintype "input"))
    )
    (net (code "49") (name "Net-(U1-STAT)") (class "Default")
      (node (ref "R1") (pin "2") (pinfunction "2_2") (pintype "passive"))
      (node (ref "U1") (pin "1") (pinfunction "STAT_1") (pintype "output"))
    )
    (net (code "50") (name "Net-(U2-XTAL1)") (class "Default")
      (node (ref "R5") (pin "1") (pinfunction "1_1") (pintype "passive"))
      (node (ref "U2") (pin "17") (pinfunction "XTAL1_17") (pintype "bidirectional"))
      (node (ref "Y2") (pin "3") (pinfunction "3_3") (pintype "passive"))
    )
    (net (code "51") (name "Net-(U2-XTAL2)") (class "Default")
      (node (ref "R5") (pin "2") (pinfunction "2_2") (pintype "passive"))
      (node (ref "U2") (pin "16") (pinfunction "XTAL2_16") (pintype "bidirectional"))
      (node (ref "Y2") (pin "1") (pinfunction "1_1") (pintype "passive"))
    )
    (net (code "52") (name "Net-(U5-ADC0)") (class "Default")
      (node (ref "R17") (pin "1") (pinfunction "1_1") (pintype "passive"))
      (node (ref "R18") (pin "2") (pinfunction "2_2") (pintype "passive"))
      (node (ref "U5") (pin "15") (pinfunction "ADC0_15") (pintype "bidirectional"))
    )
    (net (code "53") (name "Net-(U5-IO25)") (class "Default")
      (node (ref "R4") (pin "2") (pinfunction "2_2") (pintype "passive"))
      (node (ref "U5") (pin "32") (pinfunction "IO25_32") (pintype "bidirectional"))
    )
    (net (code "54") (name "Net-(U5-UART1_RXD)") (class "Default")
      (node (ref "R19") (pin "1") (pinfunction "1_1") (pintype "passive"))
      (node (ref "U5") (pin "53") (pinfunction "UART1_RXD_53") (pintype "bidirectional"))
    )
    (net (code "55") (name "Net-(U5-UART1_TXD)") (class "Default")
      (node (ref "R22") (pin "1") (pinfunction "1_1") (pintype "passive"))
      (node (ref "U5") (pin "54") (pinfunction "UART1_TXD_54") (pintype "bidirectional"))
    )
    (net (code "56") (name "Net-(U7-EN)") (class "Default")
      (node (ref "R15") (pin "1") (pinfunction "1_1") (pintype "passive"))
      (node (ref "U7") (pin "4") (pinfunction "EN_4") (pintype "input"))
    )
    (net (code "57") (name "Net-(U7-SW)") (class "Default")
      (node (ref "D12") (pin "A") (pinfunction "A_A") (pintype "passive"))
      (node (ref "L3") (pin "2") (pinfunction "2_2") (pintype "passive"))
      (node (ref "U7") (pin "1") (pinfunction "SW_1") (pintype "bidirectional"))
    )
    (net (code "58") (name "VUSB") (class "Default")
      (node (ref "C19") (pin "1") (pinfunction "1_1") (pintype "passive"))
      (node (ref "D1") (pin "+") (pinfunction "+_+") (pintype "passive"))
      (node (ref "D6") (pin "A") (pinfunction "A_A") (pintype "passive"))
      (node (ref "J5") (pin "1") (pinfunction "VCC_1") (pintype "bidirectional"))
      (node (ref "U2") (pin "2") (pinfunction "UVCC_2") (pintype "power_in"))
      (node (ref "U2") (pin "7") (pinfunction "VBUS_7") (pintype "input"))
    )
    (net (code "59") (name "unconnected-(J3-Pad5)") (class "Default")
      (node (ref "J3") (pin "5") (pinfunction "5_5") (pintype "bidirectional"))
    )
    (net (code "60") (name "unconnected-(J3-Pad6)") (class "Default")
      (node (ref "J3") (pin "6") (pinfunction "6_6") (pintype "bidirectional"))
    )
    (net (code "61") (name "unconnected-(J3-Pad7)") (class "Default")
      (node (ref "J3") (pin "7") (pinfunction "7_7") (pintype "bidirectional"))
    )
    (net (code "62") (name "unconnected-(J3-Pad8)") (class "Default")
      (node (ref "J3") (pin "8") (pinfunction "8_8") (pintype "bidirectional"))
    )
    (net (code "63") (name "unconnected-(J5-ID-Pad4)") (class "Default")
      (node (ref "J5") (pin "4") (pinfunction "ID_4") (pintype "bidirectional"))
    )
    (net (code "64") (name "unconnected-(U2-(ADC0)PF0-Pad41)") (class "Default")
      (node (ref "U2") (pin "41") (pinfunction "(ADC0)PF0_41") (pintype "bidirectional"))
    )
    (net (code "65") (name "unconnected-(U2-(ADC1)PF1-Pad40)") (class "Default")
      (node (ref "U2") (pin "40") (pinfunction "(ADC1)PF1_40") (pintype "bidirectional"))
    )
    (net (code "66") (name "unconnected-(U2-(ADC4{slash}TCK)PF4-Pad39)") (class "Default")
      (node (ref "U2") (pin "39") (pinfunction "(ADC4/TCK)PF4_39") (pintype "bidirectional"))
    )
    (net (code "67") (name "unconnected-(U2-(ADC5{slash}TMS)PF5-Pad38)") (class "Default")
      (node (ref "U2") (pin "38") (pinfunction "(ADC5/TMS)PF5_38") (pintype "bidirectional"))
    )
    (net (code "68") (name "unconnected-(U2-(ADC6{slash}TDO)PF6-Pad37)") (class "Default")
      (node (ref "U2") (pin "37") (pinfunction "(ADC6/TDO)PF6_37") (pintype "bidirectional"))
    )
    (net (code "69") (name "unconnected-(U2-(ICP3{slash}CLK0{slash}OC4A)PC7-Pad32)") (class "Default")
      (node (ref "U2") (pin "32") (pinfunction "(ICP3/CLK0/OC4A)PC7_32") (pintype "bidirectional"))
    )
    (net (code "70") (name "unconnected-(U2-(PCINT5{slash}OC1A{slash}#OC4B{slash}ADC12)PB5-Pad29)") (class "Default")
      (node (ref "U2") (pin "29") (pinfunction "(PCINT5/OC1A/#OC4B/ADC12)PB5_29") (pintype "bidirectional"))
    )
    (net (code "71") (name "unconnected-(U2-(PCINT6{slash}OC1B{slash}OC4B{slash}ADC13)PB6-Pad30)") (class "Default")
      (node (ref "U2") (pin "30") (pinfunction "(PCINT6/OC1B/OC4B/ADC13)PB6_30") (pintype "bidirectional"))
    )
    (net (code "72") (name "unconnected-(U2-(PCINT7{slash}OC0A{slash}OC1C{slash}#RTS)PB7-Pad12)") (class "Default")
      (node (ref "U2") (pin "12") (pinfunction "(PCINT7/OC0A/OC1C/#RTS)PB7_12") (pintype "bidirectional"))
    )
    (net (code "73") (name "unconnected-(U2-(SS{slash}PCINT0)PB0-Pad8)") (class "Default")
      (node (ref "U2") (pin "8") (pinfunction "(SS/PCINT0)PB0_8") (pintype "bidirectional"))
    )
    (net (code "74") (name "unconnected-(U2-(T1{slash}#OC4D{slash}ADC9)PD6-Pad26)") (class "Default")
      (node (ref "U2") (pin "26") (pinfunction "(T1/#OC4D/ADC9)PD6_26") (pintype "bidirectional"))
    )
    (net (code "75") (name "unconnected-(U2-(XCK1{slash}#CTS)PD5-Pad22)") (class "Default")
      (node (ref "U2") (pin "22") (pinfunction "(XCK1/#CTS)PD5_22") (pintype "bidirectional"))
    )
    (net (code "76") (name "unconnected-(U4-VPP-Pad6)") (class "Default")
      (node (ref "U4") (pin "6") (pinfunction "VPP_6") (pintype "bidirectional"))
    )
    (net (code "77") (name "unconnected-(U5-ADC1-Pad16)") (class "Default")
      (node (ref "U5") (pin "16") (pinfunction "ADC1_16") (pintype "bidirectional"))
    )
    (net (code "78") (name "unconnected-(U5-HST_RXD-Pad38)") (class "Default")
      (node (ref "U5") (pin "38") (pinfunction "HST_RXD_38") (pintype "bidirectional"))
    )
    (net (code "79") (name "unconnected-(U5-HST_TXD-Pad37)") (class "Default")
      (node (ref "U5") (pin "37") (pinfunction "HST_TXD_37") (pintype "bidirectional"))
    )
    (net (code "80") (name "unconnected-(U5-I2C2_SCL-Pad1)") (class "Default")
      (node (ref "U5") (pin "1") (pinfunction "I2C2_SCL_1") (pintype "bidirectional"))
    )
    (net (code "81") (name "unconnected-(U5-I2C2_SDA-Pad2)") (class "Default")
      (node (ref "U5") (pin "2") (pinfunction "I2C2_SDA_2") (pintype "bidirectional"))
    )
    (net (code "82") (name "unconnected-(U5-IO26-Pad25)") (class "Default")
      (node (ref "U5") (pin "25") (pinfunction "IO26_25") (pintype "bidirectional"))
    )
    (net (code "83") (name "unconnected-(U5-IO27-Pad26)") (class "Default")
      (node (ref "U5") (pin "26") (pinfunction "IO27_26") (pintype "bidirectional"))
    )
    (net (code "84") (name "unconnected-(U5-IO28-Pad30)") (class "Default")
      (node (ref "U5") (pin "30") (pinfunction "IO28_30") (pintype "bidirectional"))
    )
    (net (code "85") (name "unconnected-(U5-IO29-Pad24)") (class "Default")
      (node (ref "U5") (pin "24") (pinfunction "IO29_24") (pintype "bidirectional"))
    )
    (net (code "86") (name "unconnected-(U5-IO30-Pad31)") (class "Default")
      (node (ref "U5") (pin "31") (pinfunction "IO30_31") (pintype "bidirectional"))
    )
    (net (code "87") (name "unconnected-(U5-LCD_CS-Pad19)") (class "Default")
      (node (ref "U5") (pin "19") (pinfunction "LCD_CS_19") (pintype "bidirectional"))
    )
    (net (code "88") (name "unconnected-(U5-LCD_DIO-Pad21)") (class "Default")
      (node (ref "U5") (pin "21") (pinfunction "LCD_DIO_21") (pintype "bidirectional"))
    )
    (net (code "89") (name "unconnected-(U5-LCD_RST-Pad20)") (class "Default")
      (node (ref "U5") (pin "20") (pinfunction "LCD_RST_20") (pintype "bidirectional"))
    )
    (net (code "90") (name "unconnected-(U5-LCD_SCK-Pad23)") (class "Default")
      (node (ref "U5") (pin "23") (pinfunction "LCD_SCK_23") (pintype "bidirectional"))
    )
    (net (code "91") (name "unconnected-(U5-LCD_SDC-Pad22)") (class "Default")
      (node (ref "U5") (pin "22") (pinfunction "LCD_SDC_22") (pintype "bidirectional"))
    )
    (net (code "92") (name "unconnected-(U5-SD_CLK-Pad8)") (class "Default")
      (node (ref "U5") (pin "8") (pinfunction "SD_CLK_8") (pintype "bidirectional"))
    )
    (net (code "93") (name "unconnected-(U5-SD_CMD-Pad7)") (class "Default")
      (node (ref "U5") (pin "7") (pinfunction "SD_CMD_7") (pintype "bidirectional"))
    )
    (net (code "94") (name "unconnected-(U5-SD_D0-Pad6)") (class "Default")
      (node (ref "U5") (pin "6") (pinfunction "SD_D0_6") (pintype "bidirectional"))
    )
    (net (code "95") (name "unconnected-(U5-SD_D1-Pad5)") (class "Default")
      (node (ref "U5") (pin "5") (pinfunction "SD_D1_5") (pintype "bidirectional"))
    )
    (net (code "96") (name "unconnected-(U5-SD_D2-Pad4)") (class "Default")
      (node (ref "U5") (pin "4") (pinfunction "SD_D2_4") (pintype "bidirectional"))
    )
    (net (code "97") (name "unconnected-(U5-SD_D3-Pad3)") (class "Default")
      (node (ref "U5") (pin "3") (pinfunction "SD_D3_3") (pintype "bidirectional"))
    )
    (net (code "98") (name "unconnected-(U5-UART1_CTS-Pad52)") (class "Default")
      (node (ref "U5") (pin "52") (pinfunction "UART1_CTS_52") (pintype "bidirectional"))
    )
    (net (code "99") (name "unconnected-(U5-UART1_RTS-Pad51)") (class "Default")
      (node (ref "U5") (pin "51") (pinfunction "UART1_RTS_51") (pintype "bidirectional"))
    )
    (net (code "100") (name "unconnected-(U5-UART2_CTS-Pad48)") (class "Default")
      (node (ref "U5") (pin "48") (pinfunction "UART2_CTS_48") (pintype "bidirectional"))
    )
    (net (code "101") (name "unconnected-(U5-UART2_RTS-Pad47)") (class "Default")
      (node (ref "U5") (pin "47") (pinfunction "UART2_RTS_47") (pintype "bidirectional"))
    )
    (net (code "102") (name "unconnected-(U5-USB_N-Pad35)") (class "Default")
      (node (ref "U5") (pin "35") (pinfunction "USB_N_35") (pintype "bidirectional"))
    )
    (net (code "103") (name "unconnected-(U5-USB_P-Pad36)") (class "Default")
      (node (ref "U5") (pin "36") (pinfunction "USB_P_36") (pintype "bidirectional"))
    )
    (net (code "104") (name "unconnected-(U5-VUSB-Pad17)") (class "Default")
      (node (ref "U5") (pin "17") (pinfunction "VUSB_17") (pintype "bidirectional"))
    )
  )
)
